# hw4.net
KiCad netlist of a schematic drawn in EAGLE
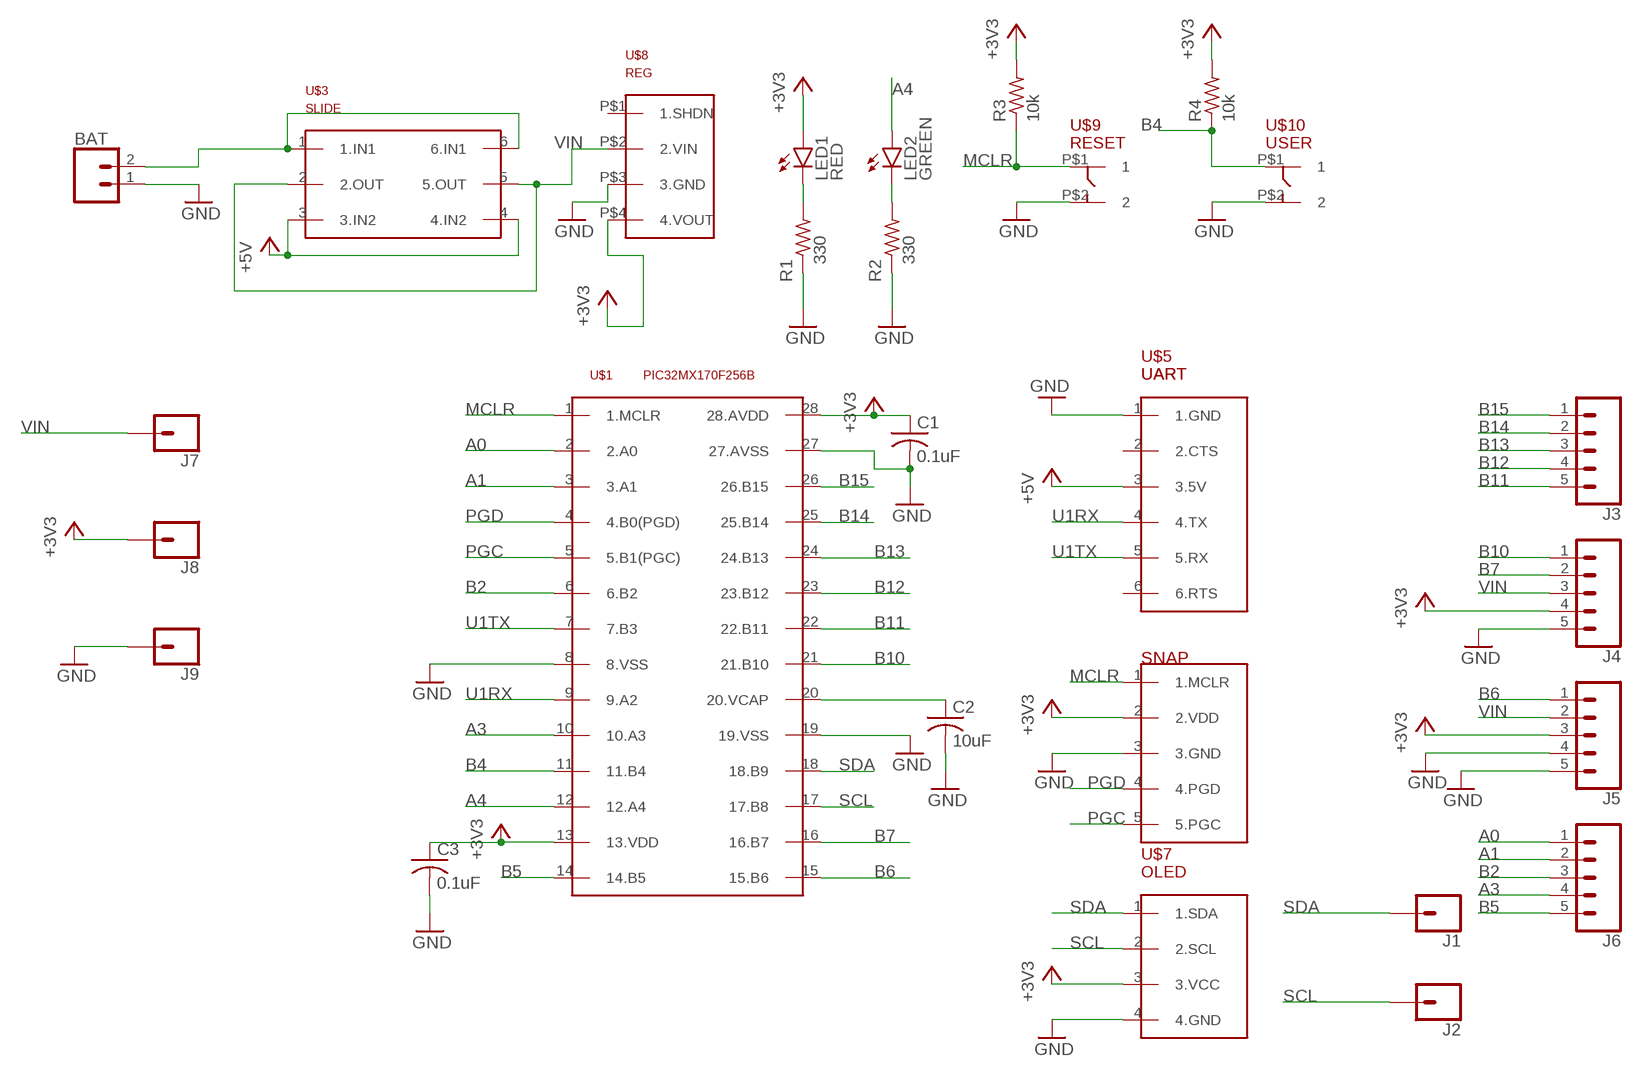
[diagram p0: schematic, sheet 1]

(export (version "E")
  (design (tool "Eeschema 10.0.6"))
  (components
    (comp (ref "BAT")
      (value "CONN_02")
      (footprint "eagle-import:1X02")
      (libsource (lib "eagle-import") (part "CONN_02"))
    )
    (comp (ref "C1")
      (value "0.1uF")
      (footprint "eagle-import:C025-024X044")
      (libsource (lib "eagle-import") (part "C-US025-024X044"))
    )
    (comp (ref "C2")
      (value "10uF")
      (footprint "eagle-import:C025-024X044")
      (libsource (lib "eagle-import") (part "C-US025-024X044"))
    )
    (comp (ref "C3")
      (value "0.1uF")
      (footprint "eagle-import:C025-024X044")
      (libsource (lib "eagle-import") (part "C-US025-024X044"))
    )
    (comp (ref "J1")
      (value "CONN_01")
      (footprint "eagle-import:1X01")
      (libsource (lib "eagle-import") (part "CONN_01"))
    )
    (comp (ref "J2")
      (value "CONN_01")
      (footprint "eagle-import:1X01")
      (libsource (lib "eagle-import") (part "CONN_01"))
    )
    (comp (ref "J3")
      (value "CONN_05")
      (footprint "eagle-import:1X05")
      (libsource (lib "eagle-import") (part "CONN_05"))
    )
    (comp (ref "J4")
      (value "CONN_05")
      (footprint "eagle-import:1X05")
      (libsource (lib "eagle-import") (part "CONN_05"))
    )
    (comp (ref "J5")
      (value "CONN_05")
      (footprint "eagle-import:1X05")
      (libsource (lib "eagle-import") (part "CONN_05"))
    )
    (comp (ref "J6")
      (value "CONN_05")
      (footprint "eagle-import:1X05")
      (libsource (lib "eagle-import") (part "CONN_05"))
    )
    (comp (ref "J7")
      (value "CONN_01")
      (footprint "eagle-import:1X01")
      (libsource (lib "eagle-import") (part "CONN_01"))
    )
    (comp (ref "J8")
      (value "CONN_01")
      (footprint "eagle-import:1X01")
      (libsource (lib "eagle-import") (part "CONN_01"))
    )
    (comp (ref "J9")
      (value "CONN_01")
      (footprint "eagle-import:1X01")
      (libsource (lib "eagle-import") (part "CONN_01"))
    )
    (comp (ref "LED1")
      (value "RED")
      (footprint "eagle-import:LED3MM")
      (libsource (lib "eagle-import") (part "LED3MM"))
    )
    (comp (ref "LED2")
      (value "GREEN")
      (footprint "eagle-import:LED3MM")
      (libsource (lib "eagle-import") (part "LED3MM"))
    )
    (comp (ref "R1")
      (value "330")
      (footprint "eagle-import:0207_7")
      (libsource (lib "eagle-import") (part "R-US_0207/7"))
    )
    (comp (ref "R2")
      (value "330")
      (footprint "eagle-import:0207_7")
      (libsource (lib "eagle-import") (part "R-US_0207/7"))
    )
    (comp (ref "R3")
      (value "10k")
      (footprint "eagle-import:0207_2V")
      (libsource (lib "eagle-import") (part "R-US_0207/2V"))
    )
    (comp (ref "R4")
      (value "10k")
      (footprint "eagle-import:0207_2V")
      (libsource (lib "eagle-import") (part "R-US_0207/2V"))
    )
    (comp (ref "U$1")
      (value "PIC32MX170F256B")
      (footprint "eagle-import:DIL28-3")
      (libsource (lib "eagle-import") (part "PIC32MX170F256B"))
    )
    (comp (ref "U$3")
      (value "SLIDE")
      (footprint "eagle-import:SLIDE")
      (libsource (lib "eagle-import") (part "SLIDE"))
    )
    (comp (ref "U$5")
      (value "UART")
      (footprint "eagle-import:UART")
      (libsource (lib "eagle-import") (part "UART"))
    )
    (comp (ref "U$6")
      (value "SNAP")
      (footprint "eagle-import:SNAP")
      (libsource (lib "eagle-import") (part "SNAP"))
    )
    (comp (ref "U$7")
      (value "OLED")
      (footprint "eagle-import:OLED")
      (libsource (lib "eagle-import") (part "OLED"))
    )
    (comp (ref "U$8")
      (value "REG")
      (footprint "eagle-import:REG")
      (libsource (lib "eagle-import") (part "REG"))
    )
    (comp (ref "U$9")
      (value "RESET")
      (footprint "eagle-import:PUSH")
      (libsource (lib "eagle-import") (part "PUSH"))
    )
    (comp (ref "U$10")
      (value "USER")
      (footprint "eagle-import:PUSH")
      (libsource (lib "eagle-import") (part "PUSH"))
    )
  )
  (nets
    (net (code "1") (name "+3V3") (class "Default")
      (node (ref "C1") (pin "1") (pinfunction "1_1") (pintype "passive"))
      (node (ref "C3") (pin "1") (pinfunction "1_1") (pintype "passive"))
      (node (ref "J4") (pin "4") (pinfunction "4_4") (pintype "passive"))
      (node (ref "J5") (pin "3") (pinfunction "3_3") (pintype "passive"))
      (node (ref "J8") (pin "1") (pinfunction "1_1") (pintype "passive"))
      (node (ref "LED1") (pin "A") (pinfunction "A_A") (pintype "passive"))
      (node (ref "R3") (pin "2") (pinfunction "2_2") (pintype "passive"))
      (node (ref "R4") (pin "2") (pinfunction "2_2") (pintype "passive"))
      (node (ref "U$1") (pin "13") (pinfunction "13.VDD_13") (pintype "bidirectional"))
      (node (ref "U$1") (pin "28") (pinfunction "28.AVDD_28") (pintype "bidirectional"))
      (node (ref "U$6") (pin "2") (pinfunction "2.VDD_2") (pintype "bidirectional"))
      (node (ref "U$7") (pin "3") (pinfunction "3.VCC_3") (pintype "bidirectional"))
      (node (ref "U$8") (pin "P$4") (pinfunction "4.VOUT_P$4") (pintype "bidirectional"))
    )
    (net (code "2") (name "+5V") (class "Default")
      (node (ref "U$3") (pin "3") (pinfunction "3.IN2_3") (pintype "bidirectional"))
      (node (ref "U$3") (pin "4") (pinfunction "4.IN2_4") (pintype "bidirectional"))
      (node (ref "U$5") (pin "3") (pinfunction "3.5V_3") (pintype "bidirectional"))
    )
    (net (code "3") (name "/A0") (class "Default")
      (node (ref "J6") (pin "1") (pinfunction "1_1") (pintype "passive"))
      (node (ref "U$1") (pin "2") (pinfunction "2.A0_2") (pintype "bidirectional"))
    )
    (net (code "4") (name "/A1") (class "Default")
      (node (ref "J6") (pin "2") (pinfunction "2_2") (pintype "passive"))
      (node (ref "U$1") (pin "3") (pinfunction "3.A1_3") (pintype "bidirectional"))
    )
    (net (code "5") (name "/A3") (class "Default")
      (node (ref "J6") (pin "4") (pinfunction "4_4") (pintype "passive"))
      (node (ref "U$1") (pin "10") (pinfunction "10.A3_10") (pintype "bidirectional"))
    )
    (net (code "6") (name "/A4") (class "Default")
      (node (ref "LED2") (pin "A") (pinfunction "A_A") (pintype "passive"))
      (node (ref "U$1") (pin "12") (pinfunction "12.A4_12") (pintype "bidirectional"))
    )
    (net (code "7") (name "/B2") (class "Default")
      (node (ref "J6") (pin "3") (pinfunction "3_3") (pintype "passive"))
      (node (ref "U$1") (pin "6") (pinfunction "6.B2_6") (pintype "bidirectional"))
    )
    (net (code "8") (name "/B4") (class "Default")
      (node (ref "R4") (pin "1") (pinfunction "1_1") (pintype "passive"))
      (node (ref "U$1") (pin "11") (pinfunction "11.B4_11") (pintype "bidirectional"))
      (node (ref "U$10") (pin "P$1") (pinfunction "1_P$1") (pintype "bidirectional"))
    )
    (net (code "9") (name "/B5") (class "Default")
      (node (ref "J6") (pin "5") (pinfunction "5_5") (pintype "passive"))
      (node (ref "U$1") (pin "14") (pinfunction "14.B5_14") (pintype "bidirectional"))
    )
    (net (code "10") (name "/B6") (class "Default")
      (node (ref "J5") (pin "1") (pinfunction "1_1") (pintype "passive"))
      (node (ref "U$1") (pin "15") (pinfunction "15.B6_15") (pintype "bidirectional"))
    )
    (net (code "11") (name "/B7") (class "Default")
      (node (ref "J4") (pin "2") (pinfunction "2_2") (pintype "passive"))
      (node (ref "U$1") (pin "16") (pinfunction "16.B7_16") (pintype "bidirectional"))
    )
    (net (code "12") (name "/B10") (class "Default")
      (node (ref "J4") (pin "1") (pinfunction "1_1") (pintype "passive"))
      (node (ref "U$1") (pin "21") (pinfunction "21.B10_21") (pintype "bidirectional"))
    )
    (net (code "13") (name "/B11") (class "Default")
      (node (ref "J3") (pin "5") (pinfunction "5_5") (pintype "passive"))
      (node (ref "U$1") (pin "22") (pinfunction "22.B11_22") (pintype "bidirectional"))
    )
    (net (code "14") (name "/B12") (class "Default")
      (node (ref "J3") (pin "4") (pinfunction "4_4") (pintype "passive"))
      (node (ref "U$1") (pin "23") (pinfunction "23.B12_23") (pintype "bidirectional"))
    )
    (net (code "15") (name "/B13") (class "Default")
      (node (ref "J3") (pin "3") (pinfunction "3_3") (pintype "passive"))
      (node (ref "U$1") (pin "24") (pinfunction "24.B13_24") (pintype "bidirectional"))
    )
    (net (code "16") (name "/B14") (class "Default")
      (node (ref "J3") (pin "2") (pinfunction "2_2") (pintype "passive"))
      (node (ref "U$1") (pin "25") (pinfunction "25.B14_25") (pintype "bidirectional"))
    )
    (net (code "17") (name "/B15") (class "Default")
      (node (ref "J3") (pin "1") (pinfunction "1_1") (pintype "passive"))
      (node (ref "U$1") (pin "26") (pinfunction "26.B15_26") (pintype "bidirectional"))
    )
    (net (code "18") (name "/MCLR") (class "Default")
      (node (ref "R3") (pin "1") (pinfunction "1_1") (pintype "passive"))
      (node (ref "U$1") (pin "1") (pinfunction "1.MCLR_1") (pintype "bidirectional"))
      (node (ref "U$6") (pin "1") (pinfunction "1.MCLR_1") (pintype "bidirectional"))
      (node (ref "U$9") (pin "P$1") (pinfunction "1_P$1") (pintype "bidirectional"))
    )
    (net (code "19") (name "/PGC") (class "Default")
      (node (ref "U$1") (pin "5") (pinfunction "5.B1(PGC)_5") (pintype "bidirectional"))
      (node (ref "U$6") (pin "5") (pinfunction "5.PGC_5") (pintype "bidirectional"))
    )
    (net (code "20") (name "/PGD") (class "Default")
      (node (ref "U$1") (pin "4") (pinfunction "4.B0(PGD)_4") (pintype "bidirectional"))
      (node (ref "U$6") (pin "4") (pinfunction "4.PGD_4") (pintype "bidirectional"))
    )
    (net (code "21") (name "/SCL") (class "Default")
      (node (ref "J2") (pin "1") (pinfunction "1_1") (pintype "passive"))
      (node (ref "U$1") (pin "17") (pinfunction "17.B8_17") (pintype "bidirectional"))
      (node (ref "U$7") (pin "2") (pinfunction "2.SCL_2") (pintype "bidirectional"))
    )
    (net (code "22") (name "/SDA") (class "Default")
      (node (ref "J1") (pin "1") (pinfunction "1_1") (pintype "passive"))
      (node (ref "U$1") (pin "18") (pinfunction "18.B9_18") (pintype "bidirectional"))
      (node (ref "U$7") (pin "1") (pinfunction "1.SDA_1") (pintype "bidirectional"))
    )
    (net (code "23") (name "/U1RX") (class "Default")
      (node (ref "U$1") (pin "9") (pinfunction "9.A2_9") (pintype "bidirectional"))
      (node (ref "U$5") (pin "4") (pinfunction "4.TX_4") (pintype "bidirectional"))
    )
    (net (code "24") (name "/U1TX") (class "Default")
      (node (ref "U$1") (pin "7") (pinfunction "7.B3_7") (pintype "bidirectional"))
      (node (ref "U$5") (pin "5") (pinfunction "5.RX_5") (pintype "bidirectional"))
    )
    (net (code "25") (name "/VIN") (class "Default")
      (node (ref "J4") (pin "3") (pinfunction "3_3") (pintype "passive"))
      (node (ref "J5") (pin "2") (pinfunction "2_2") (pintype "passive"))
      (node (ref "J7") (pin "1") (pinfunction "1_1") (pintype "passive"))
      (node (ref "U$3") (pin "2") (pinfunction "2.OUT_2") (pintype "bidirectional"))
      (node (ref "U$3") (pin "5") (pinfunction "5.OUT_5") (pintype "bidirectional"))
      (node (ref "U$8") (pin "P$2") (pinfunction "2.VIN_P$2") (pintype "bidirectional"))
    )
    (net (code "26") (name "GND") (class "Default")
      (node (ref "BAT") (pin "1") (pinfunction "1_1") (pintype "passive"))
      (node (ref "C1") (pin "2") (pinfunction "2_2") (pintype "passive"))
      (node (ref "C2") (pin "2") (pinfunction "2_2") (pintype "passive"))
      (node (ref "C3") (pin "2") (pinfunction "2_2") (pintype "passive"))
      (node (ref "J4") (pin "5") (pinfunction "5_5") (pintype "passive"))
      (node (ref "J5") (pin "4") (pinfunction "4_4") (pintype "passive"))
      (node (ref "J5") (pin "5") (pinfunction "5_5") (pintype "passive"))
      (node (ref "J9") (pin "1") (pinfunction "1_1") (pintype "passive"))
      (node (ref "R1") (pin "1") (pinfunction "1_1") (pintype "passive"))
      (node (ref "R2") (pin "1") (pinfunction "1_1") (pintype "passive"))
      (node (ref "U$1") (pin "19") (pinfunction "19.VSS_19") (pintype "bidirectional"))
      (node (ref "U$1") (pin "27") (pinfunction "27.AVSS_27") (pintype "bidirectional"))
      (node (ref "U$1") (pin "8") (pinfunction "8.VSS_8") (pintype "bidirectional"))
      (node (ref "U$10") (pin "P$2") (pinfunction "2_P$2") (pintype "bidirectional"))
      (node (ref "U$5") (pin "1") (pinfunction "1.GND_1") (pintype "bidirectional"))
      (node (ref "U$6") (pin "3") (pinfunction "3.GND_3") (pintype "bidirectional"))
      (node (ref "U$7") (pin "4") (pinfunction "4.GND_4") (pintype "bidirectional"))
      (node (ref "U$8") (pin "P$3") (pinfunction "3.GND_P$3") (pintype "bidirectional"))
      (node (ref "U$9") (pin "P$2") (pinfunction "2_P$2") (pintype "bidirectional"))
    )
    (net (code "27") (name "Net-(LED1-C)") (class "Default")
      (node (ref "LED1") (pin "K") (pinfunction "C_K") (pintype "passive"))
      (node (ref "R1") (pin "2") (pinfunction "2_2") (pintype "passive"))
    )
    (net (code "28") (name "Net-(LED2-C)") (class "Default")
      (node (ref "LED2") (pin "K") (pinfunction "C_K") (pintype "passive"))
      (node (ref "R2") (pin "2") (pinfunction "2_2") (pintype "passive"))
    )
    (net (code "29") (name "Net-(U$1-20.VCAP)") (class "Default")
      (node (ref "C2") (pin "1") (pinfunction "1_1") (pintype "passive"))
      (node (ref "U$1") (pin "20") (pinfunction "20.VCAP_20") (pintype "bidirectional"))
    )
    (net (code "30") (name "Net-(U$3-1.IN1)") (class "Default")
      (node (ref "BAT") (pin "2") (pinfunction "2_2") (pintype "passive"))
      (node (ref "U$3") (pin "1") (pinfunction "1.IN1_1") (pintype "bidirectional"))
      (node (ref "U$3") (pin "6") (pinfunction "6.IN1_6") (pintype "bidirectional"))
    )
    (net (code "31") (name "unconnected-(U$5-2.CTS-Pad2)") (class "Default")
      (node (ref "U$5") (pin "2") (pinfunction "2.CTS_2") (pintype "bidirectional"))
    )
    (net (code "32") (name "unconnected-(U$5-6.RTS-Pad6)") (class "Default")
      (node (ref "U$5") (pin "6") (pinfunction "6.RTS_6") (pintype "bidirectional"))
    )
    (net (code "33") (name "unconnected-(U$8-1.SHDN-PadP$1)") (class "Default")
      (node (ref "U$8") (pin "P$1") (pinfunction "1.SHDN_P$1") (pintype "bidirectional"))
    )
  )
)
